# Power.net
KiCad netlist of a schematic drawn in Altium Designer
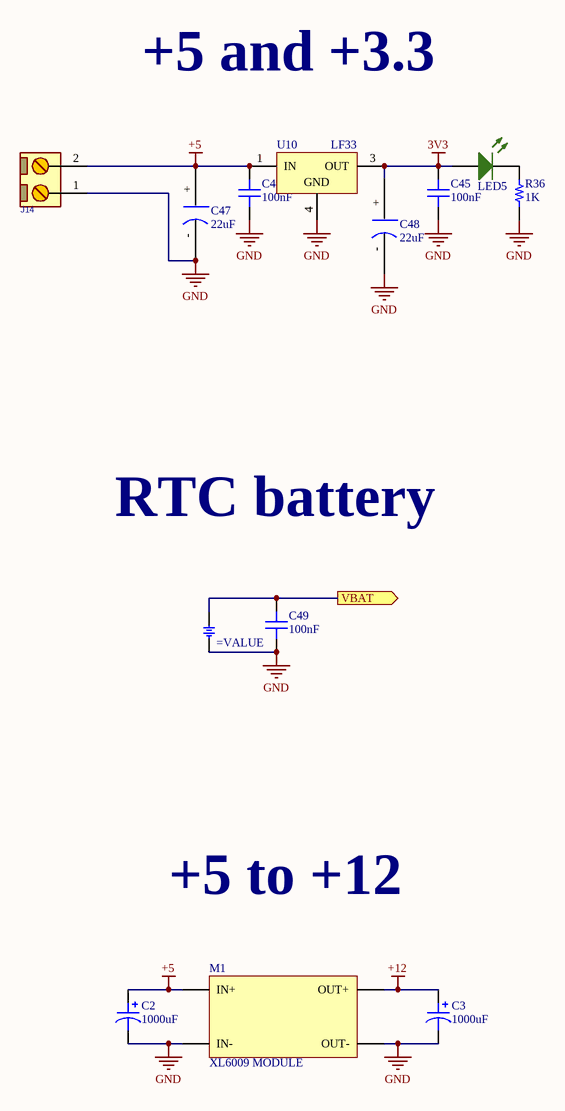
[diagram p0: Power.SchDoc]

(export (version "E")
  (design (tool "Eeschema 10.0.6"))
  (components
    (comp (ref "BT1")
      (value "~")
      (footprint "BTH1220")
      (description "Battery Holder (Open) Coin, 12.0mm 1 Cell SMD (SMT) Tab")
      (fields (field (name "PARTNUMBER") "S8411-45R"))
      (libsource (lib "Conn Battery") (part "Battery CR1220 (SMD) S8411-45R"))
    )
    (comp (ref "C2")
      (value "1000uF")
      (footprint "CAP ALTH D12.5 L5 H14")
      (description "TH Aluminum Polymer Capacitor")
      (libsource (lib "Capacitor") (part "Cap Alu TH D12.5mm L5mm H14mm"))
    )
    (comp (ref "C3")
      (value "1000uF")
      (footprint "CAP ALTH D12.5 L5 H14")
      (description "TH Aluminum Polymer Capacitor")
      (libsource (lib "Capacitor") (part "Cap Alu TH D12.5mm L5mm H14mm"))
    )
    (comp (ref "C44")
      (value "100nF")
      (footprint "CAP 0805_2012")
      (description "SMT Capacitor")
      (libsource (lib "Capacitor") (part "Cap 0805"))
    )
    (comp (ref "C45")
      (value "100nF")
      (footprint "CAP 0805_2012")
      (description "SMT Capacitor")
      (libsource (lib "Capacitor") (part "Cap 0805"))
    )
    (comp (ref "C47")
      (value "22uF")
      (footprint "CAP_6.3x7.7")
      (description "SMD Aluminum Capacitor 6.3x7.7mm")
      (libsource (lib "AlTaLibs") (part "Cap Alu 6.3x7.7mm"))
    )
    (comp (ref "C48")
      (value "22uF")
      (footprint "CAP_6.3x7.7")
      (description "SMD Aluminum Capacitor 6.3x7.7mm")
      (libsource (lib "AlTaLibs") (part "Cap Alu 6.3x7.7mm"))
    )
    (comp (ref "C49")
      (value "100nF")
      (footprint "CAP 0805_2012")
      (description "SMT Capacitor")
      (libsource (lib "Capacitor") (part "Cap 0805"))
    )
    (comp (ref "J14")
      (value "Phoenix MSTBV 2Pin")
      (footprint "PHOENIX MSTBV_2")
      (description "CONN, PHOENIX MSTBV, 5-G, 5.08mm pitch")
      (fields (field (name "PARTNUMBER") "MSTBV 2,5/ 2-G-5,08 - 1758018"))
      (libsource (lib "Conn Terminal") (part "Phoenix MSTBV 2Pin"))
    )
    (comp (ref "LED5")
      (value "LED SMD 0805 GREEN")
      (footprint "LED_0805_GREEN")
      (libsource (lib "Led") (part "LED SMD 0805 GREEN"))
    )
    (comp (ref "M1")
      (value "XL6009 MODULE")
      (footprint "XL6009")
      (description "XL6009 MODULE DC STEP UP")
      (libsource (lib "AlTaLibs_LDO") (part "XL6009 MODULE"))
    )
    (comp (ref "R36")
      (value "1K")
      (footprint "RES 0805_2012")
      (description "SMT Resistor")
      (libsource (lib "Resistor") (part "Res 0805"))
    )
    (comp (ref "U10")
      (value "LF33")
      (footprint "TO-252")
      (description "500mA, Very Low Drop (0.45V) Voltage Regulator, 3.3V, 3-Pin DPAK, Tape and Reel")
      (fields (field (name "PARTNUMBER") "LF33CDT-TR"))
      (libsource (lib "Chip") (part "LF33 (SMD)"))
    )
  )
  (nets
    (net (code "1") (name "+5") (class "Default")
      (node (ref "C2") (pin "1") (pinfunction "1_1") (pintype "passive"))
      (node (ref "C44") (pin "2") (pinfunction "2_2") (pintype "passive"))
      (node (ref "C47") (pin "+") (pinfunction "+_+") (pintype "passive"))
      (node (ref "J14") (pin "2") (pinfunction "2_2") (pintype "passive"))
      (node (ref "M1") (pin "1") (pinfunction "IN+_1") (pintype "passive"))
      (node (ref "U10") (pin "1") (pinfunction "IN_1") (pintype "power_in"))
    )
    (net (code "2") (name "+12") (class "Default")
      (node (ref "C3") (pin "1") (pinfunction "1_1") (pintype "passive"))
      (node (ref "M1") (pin "3") (pinfunction "OUT+_3") (pintype "passive"))
    )
    (net (code "3") (name "/VBAT") (class "Default")
      (node (ref "BT1") (pin "1") (pinfunction "1_1") (pintype "passive"))
      (node (ref "C49") (pin "1") (pinfunction "1_1") (pintype "passive"))
    )
    (net (code "4") (name "3V3") (class "Default")
      (node (ref "C45") (pin "2") (pinfunction "2_2") (pintype "passive"))
      (node (ref "C48") (pin "+") (pinfunction "+_+") (pintype "passive"))
      (node (ref "LED5") (pin "1") (pinfunction "A_1") (pintype "passive"))
      (node (ref "U10") (pin "3") (pinfunction "OUT_3") (pintype "power_in"))
    )
    (net (code "5") (name "GND") (class "Default")
      (node (ref "BT1") (pin "2") (pinfunction "2_2") (pintype "passive"))
      (node (ref "C2") (pin "2") (pinfunction "2_2") (pintype "passive"))
      (node (ref "C3") (pin "2") (pinfunction "2_2") (pintype "passive"))
      (node (ref "C44") (pin "1") (pinfunction "1_1") (pintype "passive"))
      (node (ref "C45") (pin "1") (pinfunction "1_1") (pintype "passive"))
      (node (ref "C47") (pin "-") (pinfunction "-_-") (pintype "passive"))
      (node (ref "C48") (pin "-") (pinfunction "-_-") (pintype "passive"))
      (node (ref "C49") (pin "2") (pinfunction "2_2") (pintype "passive"))
      (node (ref "J14") (pin "1") (pinfunction "1_1") (pintype "passive"))
      (node (ref "M1") (pin "2") (pinfunction "IN-_2") (pintype "passive"))
      (node (ref "M1") (pin "4") (pinfunction "OUT-_4") (pintype "passive"))
      (node (ref "R36") (pin "1") (pinfunction "1_1") (pintype "passive"))
      (node (ref "U10") (pin "4") (pinfunction "GND_4") (pintype "power_in"))
    )
    (net (code "6") (name "Net-(LED5-K)") (class "Default")
      (node (ref "LED5") (pin "2") (pinfunction "K_2") (pintype "passive"))
      (node (ref "R36") (pin "2") (pinfunction "2_2") (pintype "passive"))
    )
  )
)
